# DIN.net
KiCad netlist of a schematic drawn in EAGLE
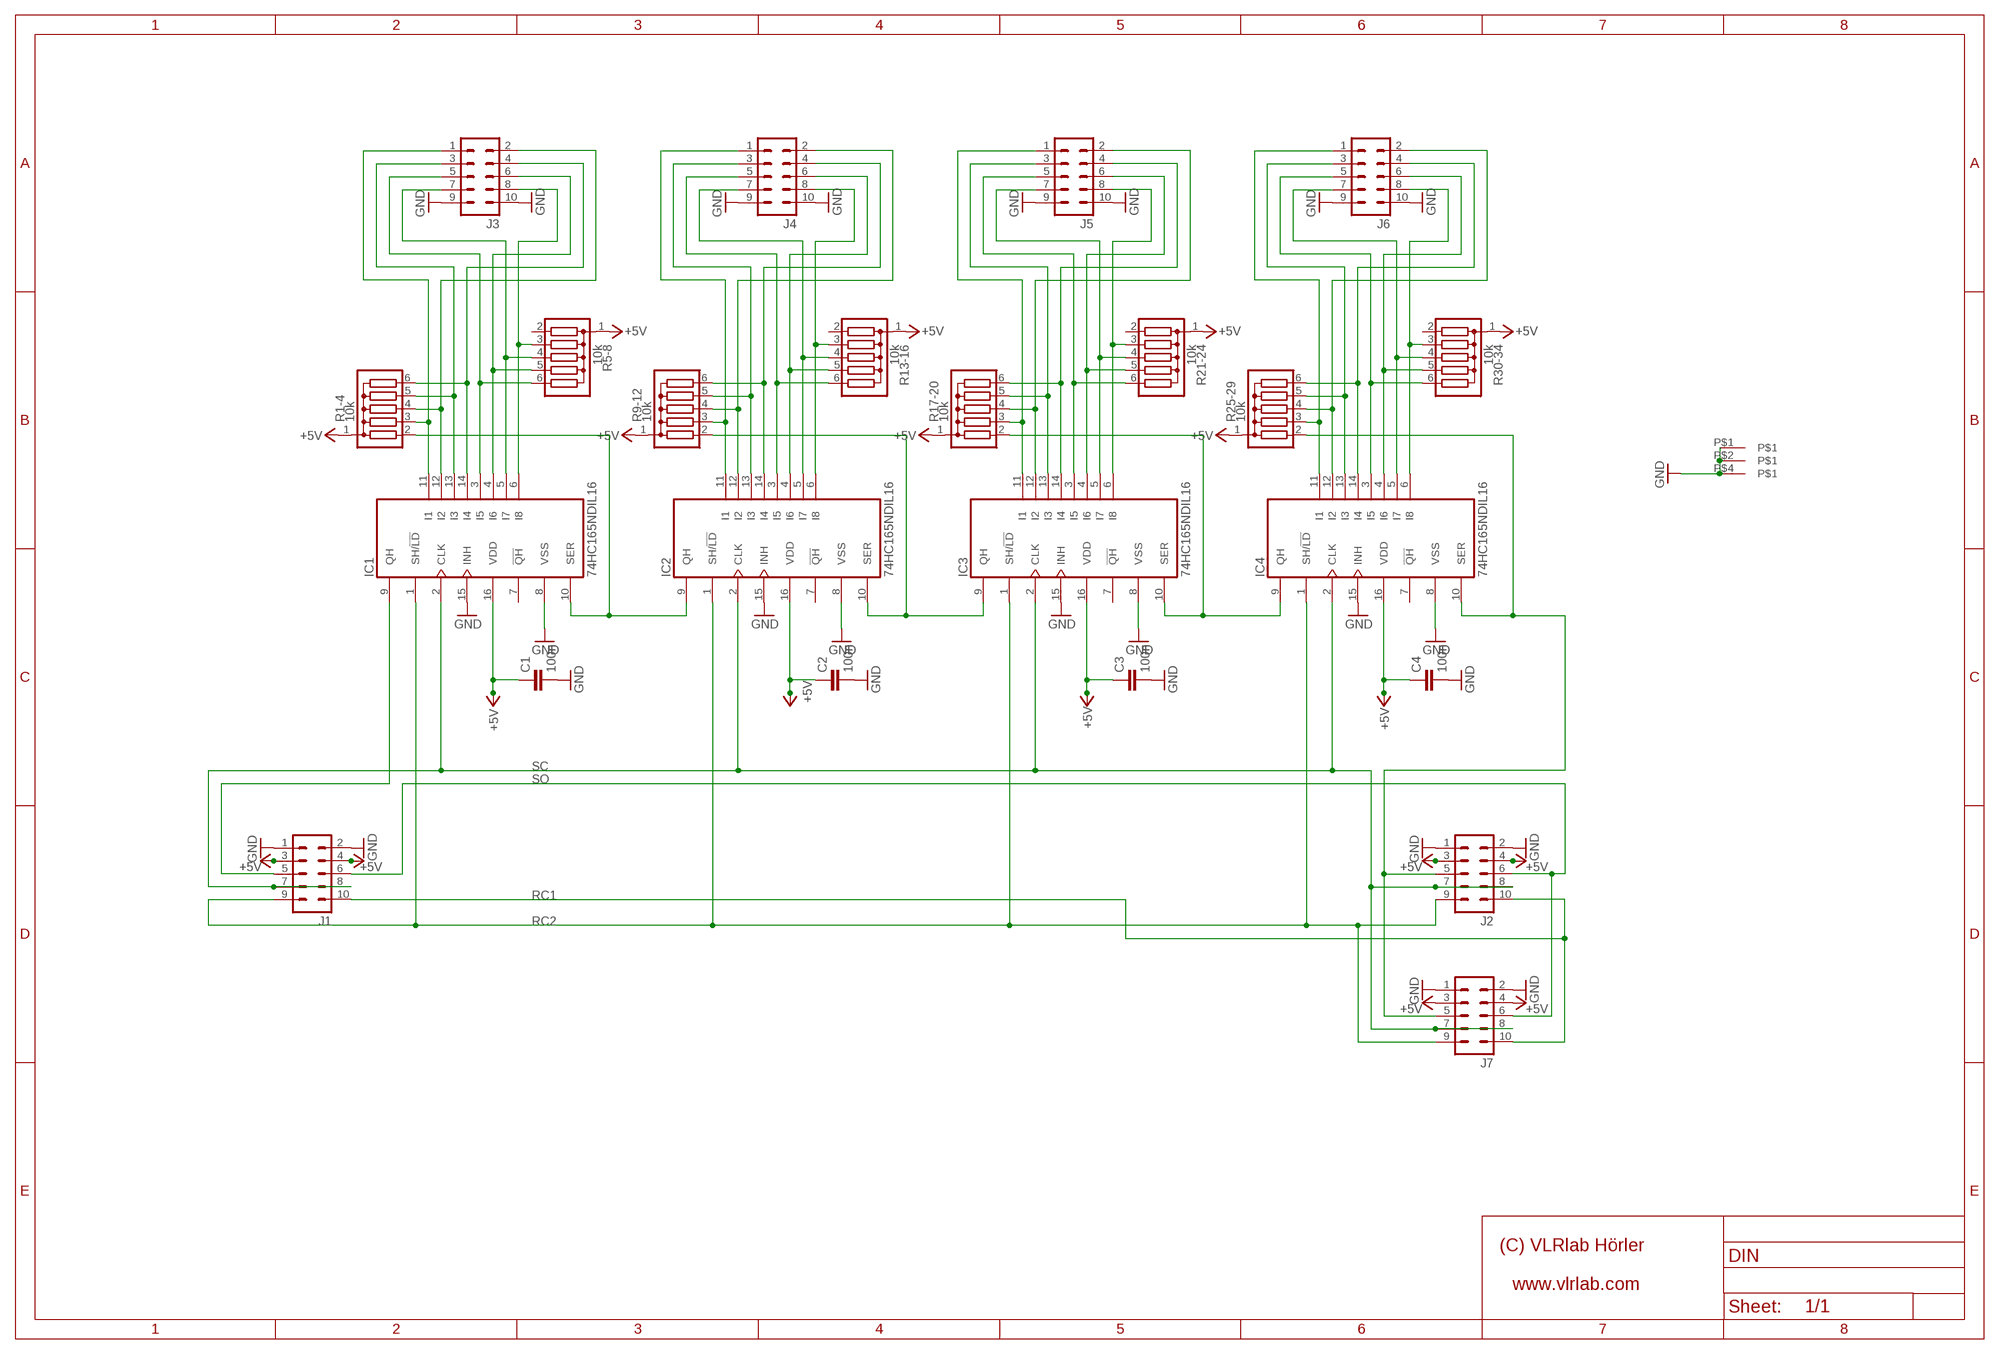
[diagram p0: schematic, sheet 1]

(export (version "E")
  (design (tool "Eeschema 10.0.6"))
  (components
    (comp (ref "C1")
      (value "100n")
      (footprint "eagle-import:C025-025X050")
      (libsource (lib "eagle-import") (part "C-EU025-025X050"))
    )
    (comp (ref "C2")
      (value "100n")
      (footprint "eagle-import:C025-025X050")
      (libsource (lib "eagle-import") (part "C-EU025-025X050"))
    )
    (comp (ref "C3")
      (value "100n")
      (footprint "eagle-import:C025-025X050")
      (libsource (lib "eagle-import") (part "C-EU025-025X050"))
    )
    (comp (ref "C4")
      (value "100n")
      (footprint "eagle-import:C025-025X050")
      (libsource (lib "eagle-import") (part "C-EU025-025X050"))
    )
    (comp (ref "IC1")
      (value "74HC165NDIL16")
      (footprint "eagle-import:DIL16")
      (libsource (lib "eagle-import") (part "74HC165NDIL16"))
    )
    (comp (ref "IC2")
      (value "74HC165NDIL16")
      (footprint "eagle-import:DIL16")
      (libsource (lib "eagle-import") (part "74HC165NDIL16"))
    )
    (comp (ref "IC3")
      (value "74HC165NDIL16")
      (footprint "eagle-import:DIL16")
      (libsource (lib "eagle-import") (part "74HC165NDIL16"))
    )
    (comp (ref "IC4")
      (value "74HC165NDIL16")
      (footprint "eagle-import:DIL16")
      (libsource (lib "eagle-import") (part "74HC165NDIL16"))
    )
    (comp (ref "J1")
      (value "ML10")
      (footprint "eagle-import:ML10")
      (libsource (lib "eagle-import") (part "ML10"))
    )
    (comp (ref "J2")
      (value "ML10")
      (footprint "eagle-import:ML10")
      (libsource (lib "eagle-import") (part "ML10"))
    )
    (comp (ref "J3")
      (value "ML10")
      (footprint "eagle-import:ML10")
      (libsource (lib "eagle-import") (part "ML10"))
    )
    (comp (ref "J4")
      (value "ML10")
      (footprint "eagle-import:ML10")
      (libsource (lib "eagle-import") (part "ML10"))
    )
    (comp (ref "J5")
      (value "ML10")
      (footprint "eagle-import:ML10")
      (libsource (lib "eagle-import") (part "ML10"))
    )
    (comp (ref "J6")
      (value "ML10")
      (footprint "eagle-import:ML10")
      (libsource (lib "eagle-import") (part "ML10"))
    )
    (comp (ref "J7")
      (value "ML10")
      (footprint "eagle-import:ML10")
      (libsource (lib "eagle-import") (part "ML10"))
    )
    (comp (ref "R1-4")
      (value "10k")
      (footprint "eagle-import:SIL6")
      (libsource (lib "eagle-import") (part "4306R"))
    )
    (comp (ref "R5-8")
      (value "10k")
      (footprint "eagle-import:SIL6")
      (libsource (lib "eagle-import") (part "4306R"))
    )
    (comp (ref "R9-12")
      (value "10k")
      (footprint "eagle-import:SIL6")
      (libsource (lib "eagle-import") (part "4306R"))
    )
    (comp (ref "R13-16")
      (value "10k")
      (footprint "eagle-import:SIL6")
      (libsource (lib "eagle-import") (part "4306R"))
    )
    (comp (ref "R17-20")
      (value "10k")
      (footprint "eagle-import:SIL6")
      (libsource (lib "eagle-import") (part "4306R"))
    )
    (comp (ref "R21-24")
      (value "10k")
      (footprint "eagle-import:SIL6")
      (libsource (lib "eagle-import") (part "4306R"))
    )
    (comp (ref "R25-29")
      (value "10k")
      (footprint "eagle-import:SIL6")
      (libsource (lib "eagle-import") (part "4306R"))
    )
    (comp (ref "R30-34")
      (value "10k")
      (footprint "eagle-import:SIL6")
      (libsource (lib "eagle-import") (part "4306R"))
    )
    (comp (ref "U$7")
      (value "MIDIBOX_HALF")
      (footprint "eagle-import:MIDIBOX14X6")
      (libsource (lib "eagle-import") (part "MIDIBOX_HALF"))
    )
  )
  (nets
    (net (code "1") (name "+5V") (class "Default")
      (node (ref "C1") (pin "1") (pinfunction "1_1") (pintype "passive"))
      (node (ref "C2") (pin "1") (pinfunction "1_1") (pintype "passive"))
      (node (ref "C3") (pin "1") (pinfunction "1_1") (pintype "passive"))
      (node (ref "C4") (pin "1") (pinfunction "1_1") (pintype "passive"))
      (node (ref "IC1") (pin "16") (pinfunction "VDD_16") (pintype "power_in"))
      (node (ref "IC2") (pin "16") (pinfunction "VDD_16") (pintype "power_in"))
      (node (ref "IC3") (pin "16") (pinfunction "VDD_16") (pintype "power_in"))
      (node (ref "IC4") (pin "16") (pinfunction "VDD_16") (pintype "power_in"))
      (node (ref "J1") (pin "3") (pinfunction "3_3") (pintype "passive"))
      (node (ref "J1") (pin "4") (pinfunction "4_4") (pintype "passive"))
      (node (ref "J2") (pin "3") (pinfunction "3_3") (pintype "passive"))
      (node (ref "J2") (pin "4") (pinfunction "4_4") (pintype "passive"))
      (node (ref "J7") (pin "3") (pinfunction "3_3") (pintype "passive"))
      (node (ref "J7") (pin "4") (pinfunction "4_4") (pintype "passive"))
      (node (ref "R1-4") (pin "1") (pinfunction "1_1") (pintype "passive"))
      (node (ref "R13-16") (pin "1") (pinfunction "1_1") (pintype "passive"))
      (node (ref "R17-20") (pin "1") (pinfunction "1_1") (pintype "passive"))
      (node (ref "R21-24") (pin "1") (pinfunction "1_1") (pintype "passive"))
      (node (ref "R25-29") (pin "1") (pinfunction "1_1") (pintype "passive"))
      (node (ref "R30-34") (pin "1") (pinfunction "1_1") (pintype "passive"))
      (node (ref "R5-8") (pin "1") (pinfunction "1_1") (pintype "passive"))
      (node (ref "R9-12") (pin "1") (pinfunction "1_1") (pintype "passive"))
    )
    (net (code "2") (name "/RC1") (class "Default")
      (node (ref "J1") (pin "10") (pinfunction "10_10") (pintype "passive"))
      (node (ref "J2") (pin "10") (pinfunction "10_10") (pintype "passive"))
      (node (ref "J7") (pin "10") (pinfunction "10_10") (pintype "passive"))
    )
    (net (code "3") (name "/RC2") (class "Default")
      (node (ref "IC1") (pin "1") (pinfunction "SH/~{LD}_1") (pintype "input"))
      (node (ref "IC2") (pin "1") (pinfunction "SH/~{LD}_1") (pintype "input"))
      (node (ref "IC3") (pin "1") (pinfunction "SH/~{LD}_1") (pintype "input"))
      (node (ref "IC4") (pin "1") (pinfunction "SH/~{LD}_1") (pintype "input"))
      (node (ref "J1") (pin "9") (pinfunction "9_9") (pintype "passive"))
      (node (ref "J2") (pin "9") (pinfunction "9_9") (pintype "passive"))
      (node (ref "J7") (pin "9") (pinfunction "9_9") (pintype "passive"))
    )
    (net (code "4") (name "/SC") (class "Default")
      (node (ref "IC1") (pin "2") (pinfunction "CLK_2") (pintype "input"))
      (node (ref "IC2") (pin "2") (pinfunction "CLK_2") (pintype "input"))
      (node (ref "IC3") (pin "2") (pinfunction "CLK_2") (pintype "input"))
      (node (ref "IC4") (pin "2") (pinfunction "CLK_2") (pintype "input"))
      (node (ref "J1") (pin "7") (pinfunction "7_7") (pintype "passive"))
      (node (ref "J1") (pin "8") (pinfunction "8_8") (pintype "passive"))
      (node (ref "J2") (pin "7") (pinfunction "7_7") (pintype "passive"))
      (node (ref "J2") (pin "8") (pinfunction "8_8") (pintype "passive"))
      (node (ref "J7") (pin "7") (pinfunction "7_7") (pintype "passive"))
      (node (ref "J7") (pin "8") (pinfunction "8_8") (pintype "passive"))
    )
    (net (code "5") (name "/SO") (class "Default")
      (node (ref "J1") (pin "6") (pinfunction "6_6") (pintype "passive"))
      (node (ref "J2") (pin "6") (pinfunction "6_6") (pintype "passive"))
      (node (ref "J7") (pin "6") (pinfunction "6_6") (pintype "passive"))
    )
    (net (code "6") (name "GND") (class "Default")
      (node (ref "C1") (pin "2") (pinfunction "2_2") (pintype "passive"))
      (node (ref "C2") (pin "2") (pinfunction "2_2") (pintype "passive"))
      (node (ref "C3") (pin "2") (pinfunction "2_2") (pintype "passive"))
      (node (ref "C4") (pin "2") (pinfunction "2_2") (pintype "passive"))
      (node (ref "IC1") (pin "15") (pinfunction "INH_15") (pintype "input"))
      (node (ref "IC1") (pin "8") (pinfunction "VSS_8") (pintype "power_in"))
      (node (ref "IC2") (pin "15") (pinfunction "INH_15") (pintype "input"))
      (node (ref "IC2") (pin "8") (pinfunction "VSS_8") (pintype "power_in"))
      (node (ref "IC3") (pin "15") (pinfunction "INH_15") (pintype "input"))
      (node (ref "IC3") (pin "8") (pinfunction "VSS_8") (pintype "power_in"))
      (node (ref "IC4") (pin "15") (pinfunction "INH_15") (pintype "input"))
      (node (ref "IC4") (pin "8") (pinfunction "VSS_8") (pintype "power_in"))
      (node (ref "J1") (pin "1") (pinfunction "1_1") (pintype "passive"))
      (node (ref "J1") (pin "2") (pinfunction "2_2") (pintype "passive"))
      (node (ref "J2") (pin "1") (pinfunction "1_1") (pintype "passive"))
      (node (ref "J2") (pin "2") (pinfunction "2_2") (pintype "passive"))
      (node (ref "J3") (pin "10") (pinfunction "10_10") (pintype "passive"))
      (node (ref "J3") (pin "9") (pinfunction "9_9") (pintype "passive"))
      (node (ref "J4") (pin "10") (pinfunction "10_10") (pintype "passive"))
      (node (ref "J4") (pin "9") (pinfunction "9_9") (pintype "passive"))
      (node (ref "J5") (pin "10") (pinfunction "10_10") (pintype "passive"))
      (node (ref "J5") (pin "9") (pinfunction "9_9") (pintype "passive"))
      (node (ref "J6") (pin "10") (pinfunction "10_10") (pintype "passive"))
      (node (ref "J6") (pin "9") (pinfunction "9_9") (pintype "passive"))
      (node (ref "J7") (pin "1") (pinfunction "1_1") (pintype "passive"))
      (node (ref "J7") (pin "2") (pinfunction "2_2") (pintype "passive"))
      (node (ref "U$7") (pin "P$1") (pinfunction "P$1_P$1") (pintype "bidirectional"))
      (node (ref "U$7") (pin "P$2") (pinfunction "P$1_P$2") (pintype "bidirectional"))
      (node (ref "U$7") (pin "P$4") (pinfunction "P$1_P$4") (pintype "bidirectional"))
    )
    (net (code "7") (name "Net-(IC1-I1)") (class "Default")
      (node (ref "IC1") (pin "11") (pinfunction "I1_11") (pintype "input"))
      (node (ref "J3") (pin "1") (pinfunction "1_1") (pintype "passive"))
      (node (ref "R1-4") (pin "3") (pinfunction "3_3") (pintype "passive"))
    )
    (net (code "8") (name "Net-(IC1-I2)") (class "Default")
      (node (ref "IC1") (pin "12") (pinfunction "I2_12") (pintype "input"))
      (node (ref "J3") (pin "2") (pinfunction "2_2") (pintype "passive"))
      (node (ref "R1-4") (pin "4") (pinfunction "4_4") (pintype "passive"))
    )
    (net (code "9") (name "Net-(IC1-I3)") (class "Default")
      (node (ref "IC1") (pin "13") (pinfunction "I3_13") (pintype "input"))
      (node (ref "J3") (pin "3") (pinfunction "3_3") (pintype "passive"))
      (node (ref "R1-4") (pin "5") (pinfunction "5_5") (pintype "passive"))
    )
    (net (code "10") (name "Net-(IC1-I4)") (class "Default")
      (node (ref "IC1") (pin "14") (pinfunction "I4_14") (pintype "input"))
      (node (ref "J3") (pin "4") (pinfunction "4_4") (pintype "passive"))
      (node (ref "R1-4") (pin "6") (pinfunction "6_6") (pintype "passive"))
    )
    (net (code "11") (name "Net-(IC1-I5)") (class "Default")
      (node (ref "IC1") (pin "3") (pinfunction "I5_3") (pintype "input"))
      (node (ref "J3") (pin "5") (pinfunction "5_5") (pintype "passive"))
      (node (ref "R5-8") (pin "6") (pinfunction "6_6") (pintype "passive"))
    )
    (net (code "12") (name "Net-(IC1-I6)") (class "Default")
      (node (ref "IC1") (pin "4") (pinfunction "I6_4") (pintype "input"))
      (node (ref "J3") (pin "6") (pinfunction "6_6") (pintype "passive"))
      (node (ref "R5-8") (pin "5") (pinfunction "5_5") (pintype "passive"))
    )
    (net (code "13") (name "Net-(IC1-I7)") (class "Default")
      (node (ref "IC1") (pin "5") (pinfunction "I7_5") (pintype "input"))
      (node (ref "J3") (pin "7") (pinfunction "7_7") (pintype "passive"))
      (node (ref "R5-8") (pin "4") (pinfunction "4_4") (pintype "passive"))
    )
    (net (code "14") (name "Net-(IC1-I8)") (class "Default")
      (node (ref "IC1") (pin "6") (pinfunction "I8_6") (pintype "input"))
      (node (ref "J3") (pin "8") (pinfunction "8_8") (pintype "passive"))
      (node (ref "R5-8") (pin "3") (pinfunction "3_3") (pintype "passive"))
    )
    (net (code "15") (name "Net-(IC1-QH)") (class "Default")
      (node (ref "IC1") (pin "9") (pinfunction "QH_9") (pintype "output"))
      (node (ref "J1") (pin "5") (pinfunction "5_5") (pintype "passive"))
    )
    (net (code "16") (name "Net-(IC1-SER)") (class "Default")
      (node (ref "IC1") (pin "10") (pinfunction "SER_10") (pintype "input"))
      (node (ref "IC2") (pin "9") (pinfunction "QH_9") (pintype "output"))
      (node (ref "R1-4") (pin "2") (pinfunction "2_2") (pintype "passive"))
    )
    (net (code "17") (name "Net-(IC2-I1)") (class "Default")
      (node (ref "IC2") (pin "11") (pinfunction "I1_11") (pintype "input"))
      (node (ref "J4") (pin "1") (pinfunction "1_1") (pintype "passive"))
      (node (ref "R9-12") (pin "3") (pinfunction "3_3") (pintype "passive"))
    )
    (net (code "18") (name "Net-(IC2-I2)") (class "Default")
      (node (ref "IC2") (pin "12") (pinfunction "I2_12") (pintype "input"))
      (node (ref "J4") (pin "2") (pinfunction "2_2") (pintype "passive"))
      (node (ref "R9-12") (pin "4") (pinfunction "4_4") (pintype "passive"))
    )
    (net (code "19") (name "Net-(IC2-I3)") (class "Default")
      (node (ref "IC2") (pin "13") (pinfunction "I3_13") (pintype "input"))
      (node (ref "J4") (pin "3") (pinfunction "3_3") (pintype "passive"))
      (node (ref "R9-12") (pin "5") (pinfunction "5_5") (pintype "passive"))
    )
    (net (code "20") (name "Net-(IC2-I4)") (class "Default")
      (node (ref "IC2") (pin "14") (pinfunction "I4_14") (pintype "input"))
      (node (ref "J4") (pin "4") (pinfunction "4_4") (pintype "passive"))
      (node (ref "R9-12") (pin "6") (pinfunction "6_6") (pintype "passive"))
    )
    (net (code "21") (name "Net-(IC2-I5)") (class "Default")
      (node (ref "IC2") (pin "3") (pinfunction "I5_3") (pintype "input"))
      (node (ref "J4") (pin "5") (pinfunction "5_5") (pintype "passive"))
      (node (ref "R13-16") (pin "6") (pinfunction "6_6") (pintype "passive"))
    )
    (net (code "22") (name "Net-(IC2-I6)") (class "Default")
      (node (ref "IC2") (pin "4") (pinfunction "I6_4") (pintype "input"))
      (node (ref "J4") (pin "6") (pinfunction "6_6") (pintype "passive"))
      (node (ref "R13-16") (pin "5") (pinfunction "5_5") (pintype "passive"))
    )
    (net (code "23") (name "Net-(IC2-I7)") (class "Default")
      (node (ref "IC2") (pin "5") (pinfunction "I7_5") (pintype "input"))
      (node (ref "J4") (pin "7") (pinfunction "7_7") (pintype "passive"))
      (node (ref "R13-16") (pin "4") (pinfunction "4_4") (pintype "passive"))
    )
    (net (code "24") (name "Net-(IC2-I8)") (class "Default")
      (node (ref "IC2") (pin "6") (pinfunction "I8_6") (pintype "input"))
      (node (ref "J4") (pin "8") (pinfunction "8_8") (pintype "passive"))
      (node (ref "R13-16") (pin "3") (pinfunction "3_3") (pintype "passive"))
    )
    (net (code "25") (name "Net-(IC2-SER)") (class "Default")
      (node (ref "IC2") (pin "10") (pinfunction "SER_10") (pintype "input"))
      (node (ref "IC3") (pin "9") (pinfunction "QH_9") (pintype "output"))
      (node (ref "R9-12") (pin "2") (pinfunction "2_2") (pintype "passive"))
    )
    (net (code "26") (name "Net-(IC3-I1)") (class "Default")
      (node (ref "IC3") (pin "11") (pinfunction "I1_11") (pintype "input"))
      (node (ref "J5") (pin "1") (pinfunction "1_1") (pintype "passive"))
      (node (ref "R17-20") (pin "3") (pinfunction "3_3") (pintype "passive"))
    )
    (net (code "27") (name "Net-(IC3-I2)") (class "Default")
      (node (ref "IC3") (pin "12") (pinfunction "I2_12") (pintype "input"))
      (node (ref "J5") (pin "2") (pinfunction "2_2") (pintype "passive"))
      (node (ref "R17-20") (pin "4") (pinfunction "4_4") (pintype "passive"))
    )
    (net (code "28") (name "Net-(IC3-I3)") (class "Default")
      (node (ref "IC3") (pin "13") (pinfunction "I3_13") (pintype "input"))
      (node (ref "J5") (pin "3") (pinfunction "3_3") (pintype "passive"))
      (node (ref "R17-20") (pin "5") (pinfunction "5_5") (pintype "passive"))
    )
    (net (code "29") (name "Net-(IC3-I4)") (class "Default")
      (node (ref "IC3") (pin "14") (pinfunction "I4_14") (pintype "input"))
      (node (ref "J5") (pin "4") (pinfunction "4_4") (pintype "passive"))
      (node (ref "R17-20") (pin "6") (pinfunction "6_6") (pintype "passive"))
    )
    (net (code "30") (name "Net-(IC3-I5)") (class "Default")
      (node (ref "IC3") (pin "3") (pinfunction "I5_3") (pintype "input"))
      (node (ref "J5") (pin "5") (pinfunction "5_5") (pintype "passive"))
      (node (ref "R21-24") (pin "6") (pinfunction "6_6") (pintype "passive"))
    )
    (net (code "31") (name "Net-(IC3-I6)") (class "Default")
      (node (ref "IC3") (pin "4") (pinfunction "I6_4") (pintype "input"))
      (node (ref "J5") (pin "6") (pinfunction "6_6") (pintype "passive"))
      (node (ref "R21-24") (pin "5") (pinfunction "5_5") (pintype "passive"))
    )
    (net (code "32") (name "Net-(IC3-I7)") (class "Default")
      (node (ref "IC3") (pin "5") (pinfunction "I7_5") (pintype "input"))
      (node (ref "J5") (pin "7") (pinfunction "7_7") (pintype "passive"))
      (node (ref "R21-24") (pin "4") (pinfunction "4_4") (pintype "passive"))
    )
    (net (code "33") (name "Net-(IC3-I8)") (class "Default")
      (node (ref "IC3") (pin "6") (pinfunction "I8_6") (pintype "input"))
      (node (ref "J5") (pin "8") (pinfunction "8_8") (pintype "passive"))
      (node (ref "R21-24") (pin "3") (pinfunction "3_3") (pintype "passive"))
    )
    (net (code "34") (name "Net-(IC3-SER)") (class "Default")
      (node (ref "IC3") (pin "10") (pinfunction "SER_10") (pintype "input"))
      (node (ref "IC4") (pin "9") (pinfunction "QH_9") (pintype "output"))
      (node (ref "R17-20") (pin "2") (pinfunction "2_2") (pintype "passive"))
    )
    (net (code "35") (name "Net-(IC4-I1)") (class "Default")
      (node (ref "IC4") (pin "11") (pinfunction "I1_11") (pintype "input"))
      (node (ref "J6") (pin "1") (pinfunction "1_1") (pintype "passive"))
      (node (ref "R25-29") (pin "3") (pinfunction "3_3") (pintype "passive"))
    )
    (net (code "36") (name "Net-(IC4-I2)") (class "Default")
      (node (ref "IC4") (pin "12") (pinfunction "I2_12") (pintype "input"))
      (node (ref "J6") (pin "2") (pinfunction "2_2") (pintype "passive"))
      (node (ref "R25-29") (pin "4") (pinfunction "4_4") (pintype "passive"))
    )
    (net (code "37") (name "Net-(IC4-I3)") (class "Default")
      (node (ref "IC4") (pin "13") (pinfunction "I3_13") (pintype "input"))
      (node (ref "J6") (pin "3") (pinfunction "3_3") (pintype "passive"))
      (node (ref "R25-29") (pin "5") (pinfunction "5_5") (pintype "passive"))
    )
    (net (code "38") (name "Net-(IC4-I4)") (class "Default")
      (node (ref "IC4") (pin "14") (pinfunction "I4_14") (pintype "input"))
      (node (ref "J6") (pin "4") (pinfunction "4_4") (pintype "passive"))
      (node (ref "R25-29") (pin "6") (pinfunction "6_6") (pintype "passive"))
    )
    (net (code "39") (name "Net-(IC4-I5)") (class "Default")
      (node (ref "IC4") (pin "3") (pinfunction "I5_3") (pintype "input"))
      (node (ref "J6") (pin "5") (pinfunction "5_5") (pintype "passive"))
      (node (ref "R30-34") (pin "6") (pinfunction "6_6") (pintype "passive"))
    )
    (net (code "40") (name "Net-(IC4-I6)") (class "Default")
      (node (ref "IC4") (pin "4") (pinfunction "I6_4") (pintype "input"))
      (node (ref "J6") (pin "6") (pinfunction "6_6") (pintype "passive"))
      (node (ref "R30-34") (pin "5") (pinfunction "5_5") (pintype "passive"))
    )
    (net (code "41") (name "Net-(IC4-I7)") (class "Default")
      (node (ref "IC4") (pin "5") (pinfunction "I7_5") (pintype "input"))
      (node (ref "J6") (pin "7") (pinfunction "7_7") (pintype "passive"))
      (node (ref "R30-34") (pin "4") (pinfunction "4_4") (pintype "passive"))
    )
    (net (code "42") (name "Net-(IC4-I8)") (class "Default")
      (node (ref "IC4") (pin "6") (pinfunction "I8_6") (pintype "input"))
      (node (ref "J6") (pin "8") (pinfunction "8_8") (pintype "passive"))
      (node (ref "R30-34") (pin "3") (pinfunction "3_3") (pintype "passive"))
    )
    (net (code "43") (name "Net-(IC4-SER)") (class "Default")
      (node (ref "IC4") (pin "10") (pinfunction "SER_10") (pintype "input"))
      (node (ref "J2") (pin "5") (pinfunction "5_5") (pintype "passive"))
      (node (ref "J7") (pin "5") (pinfunction "5_5") (pintype "passive"))
      (node (ref "R25-29") (pin "2") (pinfunction "2_2") (pintype "passive"))
    )
    (net (code "44") (name "unconnected-(IC1-~{QH}-Pad7)") (class "Default")
      (node (ref "IC1") (pin "7") (pinfunction "~{QH}_7") (pintype "output"))
    )
    (net (code "45") (name "unconnected-(IC2-~{QH}-Pad7)") (class "Default")
      (node (ref "IC2") (pin "7") (pinfunction "~{QH}_7") (pintype "output"))
    )
    (net (code "46") (name "unconnected-(IC3-~{QH}-Pad7)") (class "Default")
      (node (ref "IC3") (pin "7") (pinfunction "~{QH}_7") (pintype "output"))
    )
    (net (code "47") (name "unconnected-(IC4-~{QH}-Pad7)") (class "Default")
      (node (ref "IC4") (pin "7") (pinfunction "~{QH}_7") (pintype "output"))
    )
    (net (code "48") (name "unconnected-(R5-8-Pad2)") (class "Default")
      (node (ref "R5-8") (pin "2") (pinfunction "2_2") (pintype "passive"))
    )
    (net (code "49") (name "unconnected-(R13-16-Pad2)") (class "Default")
      (node (ref "R13-16") (pin "2") (pinfunction "2_2") (pintype "passive"))
    )
    (net (code "50") (name "unconnected-(R21-24-Pad2)") (class "Default")
      (node (ref "R21-24") (pin "2") (pinfunction "2_2") (pintype "passive"))
    )
    (net (code "51") (name "unconnected-(R30-34-Pad2)") (class "Default")
      (node (ref "R30-34") (pin "2") (pinfunction "2_2") (pintype "passive"))
    )
  )
)
